# 222.net
KiCad netlist of a schematic drawn in Altium Designer
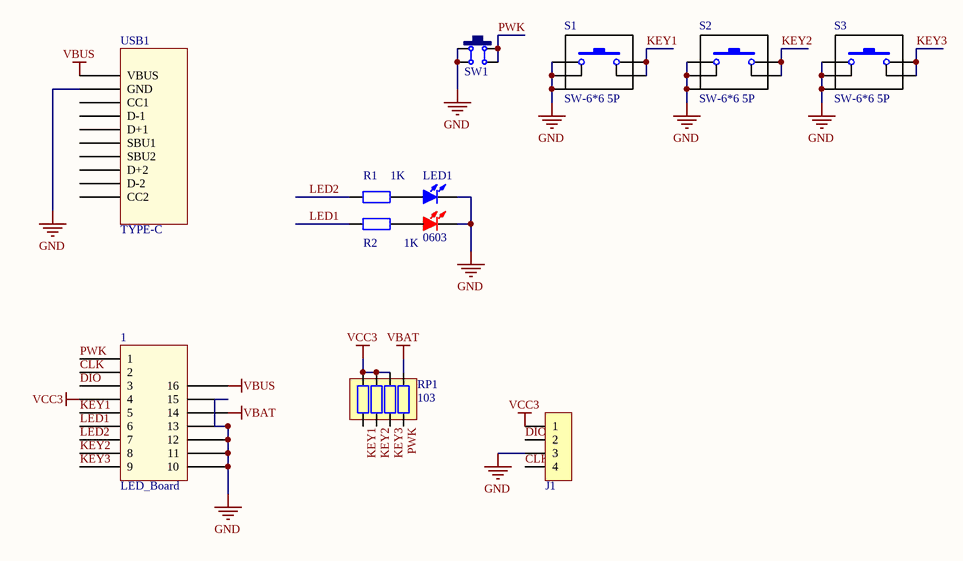
[diagram p0: 222.SchDoc]

(export (version "E")
  (design (tool "Eeschema 10.0.6"))
  (components
    (comp (ref "1") (value "LED_Board") (footprint "LED_PAD") (libsource (lib "fszhang") (part "LED_Board")))
    (comp (ref "J1")
      (value "HDR-1X4")
      (footprint "HDR2.0-LI-4P")
      (description "4P接插件")
      (libsource (lib "4.5   - 接插件-脚距2.0") (part "Header 4"))
    )
    (comp (ref "LED1")
      (value "0603")
      (footprint "LED 0603-RG")
      (description "贴片双色LED")
      (libsource (lib "9.1   - LED") (part "LED-SMD-RG"))
    )
    (comp (ref "R1")
      (value "1K")
      (footprint "R 0402_M")
      (description "贴片电阻")
      (libsource (lib "3.1   - 电阻-电容-电感") (part "R"))
    )
    (comp (ref "R2")
      (value "1K")
      (footprint "R 0402_M")
      (description "贴片电阻")
      (libsource (lib "3.1   - 电阻-电容-电感") (part "R"))
    )
    (comp (ref "RP1")
      (value "103")
      (footprint "RCA-8P4R-0402")
      (description "贴片网络排阻")
      (libsource (lib "3.1   - 电阻-电容-电感") (part "R-8P4R"))
    )
    (comp (ref "S1")
      (value "SW-6*6 5P")
      (footprint "SW6*6")
      (description "微动开关")
      (fields (field (name "PUBLISHER") "Altium Limited"))
      (libsource (lib "fszhang") (part "SW-6*6 5P"))
    )
    (comp (ref "S2")
      (value "SW-6*6 5P")
      (footprint "SW6*6")
      (description "微动开关")
      (fields (field (name "PUBLISHER") "Altium Limited"))
      (libsource (lib "fszhang") (part "SW-6*6 5P"))
    )
    (comp (ref "S3")
      (value "SW-6*6 5P")
      (footprint "SW6*6")
      (description "微动开关")
      (fields (field (name "PUBLISHER") "Altium Limited"))
      (libsource (lib "fszhang") (part "SW-6*6 5P"))
    )
    (comp (ref "SW1")
      (value "4x4x0.8")
      (footprint "TS-027A")
      (description "薄膜轻触开关")
      (libsource (lib "5.1   - 按键-开关") (part "TS-027A"))
    )
    (comp (ref "USB1") (value "TYPE-C") (footprint "TYPE-C") (libsource (lib "1") (part "USB-C")))
  )
  (nets
    (net (code "1") (name "/CLK") (class "Default")
      (node (ref "1") (pin "2") (pinfunction "2_2") (pintype "passive"))
      (node (ref "J1") (pin "4") (pinfunction "4_4") (pintype "passive"))
    )
    (net (code "2") (name "/DIO") (class "Default")
      (node (ref "1") (pin "3") (pinfunction "3_3") (pintype "passive"))
      (node (ref "J1") (pin "2") (pinfunction "2_2") (pintype "passive"))
    )
    (net (code "3") (name "/KEY1") (class "Default")
      (node (ref "1") (pin "5") (pinfunction "5_5") (pintype "passive"))
      (node (ref "RP1") (pin "1") (pinfunction "1_1") (pintype "passive"))
      (node (ref "S1") (pin "2") (pinfunction "2_2") (pintype "passive"))
      (node (ref "S1") (pin "3") (pinfunction "3_3") (pintype "passive"))
    )
    (net (code "4") (name "/KEY2") (class "Default")
      (node (ref "1") (pin "8") (pinfunction "8_8") (pintype "passive"))
      (node (ref "RP1") (pin "2") (pinfunction "2_2") (pintype "passive"))
      (node (ref "S2") (pin "2") (pinfunction "2_2") (pintype "passive"))
      (node (ref "S2") (pin "3") (pinfunction "3_3") (pintype "passive"))
    )
    (net (code "5") (name "/KEY3") (class "Default")
      (node (ref "1") (pin "9") (pinfunction "9_9") (pintype "passive"))
      (node (ref "RP1") (pin "3") (pinfunction "3_3") (pintype "passive"))
      (node (ref "S3") (pin "2") (pinfunction "2_2") (pintype "passive"))
      (node (ref "S3") (pin "3") (pinfunction "3_3") (pintype "passive"))
    )
    (net (code "6") (name "/LED1") (class "Default")
      (node (ref "1") (pin "6") (pinfunction "6_6") (pintype "passive"))
      (node (ref "R2") (pin "1") (pinfunction "1_1") (pintype "passive"))
    )
    (net (code "7") (name "/LED2") (class "Default")
      (node (ref "1") (pin "7") (pinfunction "7_7") (pintype "passive"))
      (node (ref "R1") (pin "1") (pinfunction "1_1") (pintype "passive"))
    )
    (net (code "8") (name "/PWK") (class "Default")
      (node (ref "1") (pin "1") (pinfunction "1_1") (pintype "passive"))
      (node (ref "RP1") (pin "4") (pinfunction "4_4") (pintype "passive"))
      (node (ref "SW1") (pin "2") (pinfunction "2_2") (pintype "passive"))
      (node (ref "SW1") (pin "3") (pinfunction "3_3") (pintype "passive"))
    )
    (net (code "9") (name "GND") (class "Default")
      (node (ref "1") (pin "10") (pinfunction "10_10") (pintype "passive"))
      (node (ref "1") (pin "11") (pinfunction "11_11") (pintype "passive"))
      (node (ref "1") (pin "12") (pinfunction "12_12") (pintype "passive"))
      (node (ref "1") (pin "13") (pinfunction "13_13") (pintype "passive"))
      (node (ref "1") (pin "15") (pinfunction "15_15") (pintype "passive"))
      (node (ref "J1") (pin "3") (pinfunction "3_3") (pintype "passive"))
      (node (ref "LED1") (pin "3") (pinfunction "3_3") (pintype "passive"))
      (node (ref "LED1") (pin "4") (pinfunction "4_4") (pintype "passive"))
      (node (ref "S1") (pin "1") (pinfunction "1_1") (pintype "passive"))
      (node (ref "S1") (pin "4") (pinfunction "4_4") (pintype "passive"))
      (node (ref "S1") (pin "5") (pinfunction "5_5") (pintype "passive"))
      (node (ref "S2") (pin "1") (pinfunction "1_1") (pintype "passive"))
      (node (ref "S2") (pin "4") (pinfunction "4_4") (pintype "passive"))
      (node (ref "S2") (pin "5") (pinfunction "5_5") (pintype "passive"))
      (node (ref "S3") (pin "1") (pinfunction "1_1") (pintype "passive"))
      (node (ref "S3") (pin "4") (pinfunction "4_4") (pintype "passive"))
      (node (ref "S3") (pin "5") (pinfunction "5_5") (pintype "passive"))
      (node (ref "SW1") (pin "1") (pinfunction "1_1") (pintype "passive"))
      (node (ref "SW1") (pin "4") (pinfunction "4_4") (pintype "passive"))
      (node (ref "USB1") (pin "GND") (pinfunction "GND_GND") (pintype "passive"))
    )
    (net (code "10") (name "Net-(LED1-1-Pad2)") (class "Default")
      (node (ref "LED1") (pin "2") (pinfunction "1_2") (pintype "passive"))
      (node (ref "R2") (pin "2") (pinfunction "2_2") (pintype "passive"))
    )
    (net (code "11") (name "Net-(LED1-Pad1)") (class "Default")
      (node (ref "LED1") (pin "1") (pinfunction "1_1") (pintype "passive"))
      (node (ref "R1") (pin "2") (pinfunction "2_2") (pintype "passive"))
    )
    (net (code "12") (name "VBAT") (class "Default")
      (node (ref "1") (pin "14") (pinfunction "14_14") (pintype "passive"))
      (node (ref "RP1") (pin "5") (pinfunction "5_5") (pintype "passive"))
    )
    (net (code "13") (name "VBUS") (class "Default")
      (node (ref "1") (pin "16") (pinfunction "16_16") (pintype "passive"))
      (node (ref "USB1") (pin "VBUS") (pinfunction "VBUS_VBUS") (pintype "passive"))
    )
    (net (code "14") (name "VCC3") (class "Default")
      (node (ref "1") (pin "4") (pinfunction "4_4") (pintype "passive"))
      (node (ref "J1") (pin "1") (pinfunction "1_1") (pintype "passive"))
      (node (ref "RP1") (pin "6") (pinfunction "6_6") (pintype "passive"))
      (node (ref "RP1") (pin "7") (pinfunction "7_7") (pintype "passive"))
      (node (ref "RP1") (pin "8") (pinfunction "8_8") (pintype "passive"))
    )
    (net (code "15") (name "unconnected-(USB1-CC2-PadCC1)") (class "Default")
      (node (ref "USB1") (pin "CC1") (pinfunction "CC2_CC1") (pintype "passive"))
    )
    (net (code "16") (name "unconnected-(USB1-PadCC1)") (class "Default")
      (node (ref "USB1") (pin "CC1") (pinfunction "CC1_CC1") (pintype "passive"))
    )
    (net (code "17") (name "unconnected-(USB1-PadD+1)") (class "Default")
      (node (ref "USB1") (pin "D+1") (pinfunction "D+1_D+1") (pintype "passive"))
    )
    (net (code "18") (name "unconnected-(USB1-PadD+2)") (class "Default")
      (node (ref "USB1") (pin "D+2") (pinfunction "D+2_D+2") (pintype "passive"))
    )
    (net (code "19") (name "unconnected-(USB1-PadD-1)") (class "Default")
      (node (ref "USB1") (pin "D-1") (pinfunction "D-1_D-1") (pintype "passive"))
    )
    (net (code "20") (name "unconnected-(USB1-PadD-2)") (class "Default")
      (node (ref "USB1") (pin "D-2") (pinfunction "D-2_D-2") (pintype "passive"))
    )
    (net (code "21") (name "unconnected-(USB1-PadSBU1)") (class "Default")
      (node (ref "USB1") (pin "SBU1") (pinfunction "SBU1_SBU1") (pintype "passive"))
    )
    (net (code "22") (name "unconnected-(USB1-PadSBU2)") (class "Default")
      (node (ref "USB1") (pin "SBU2") (pinfunction "SBU2_SBU2") (pintype "passive"))
    )
  )
)
